# uBristleBot-Pogo-Programmer.net
KiCad netlist of a schematic drawn in EAGLE
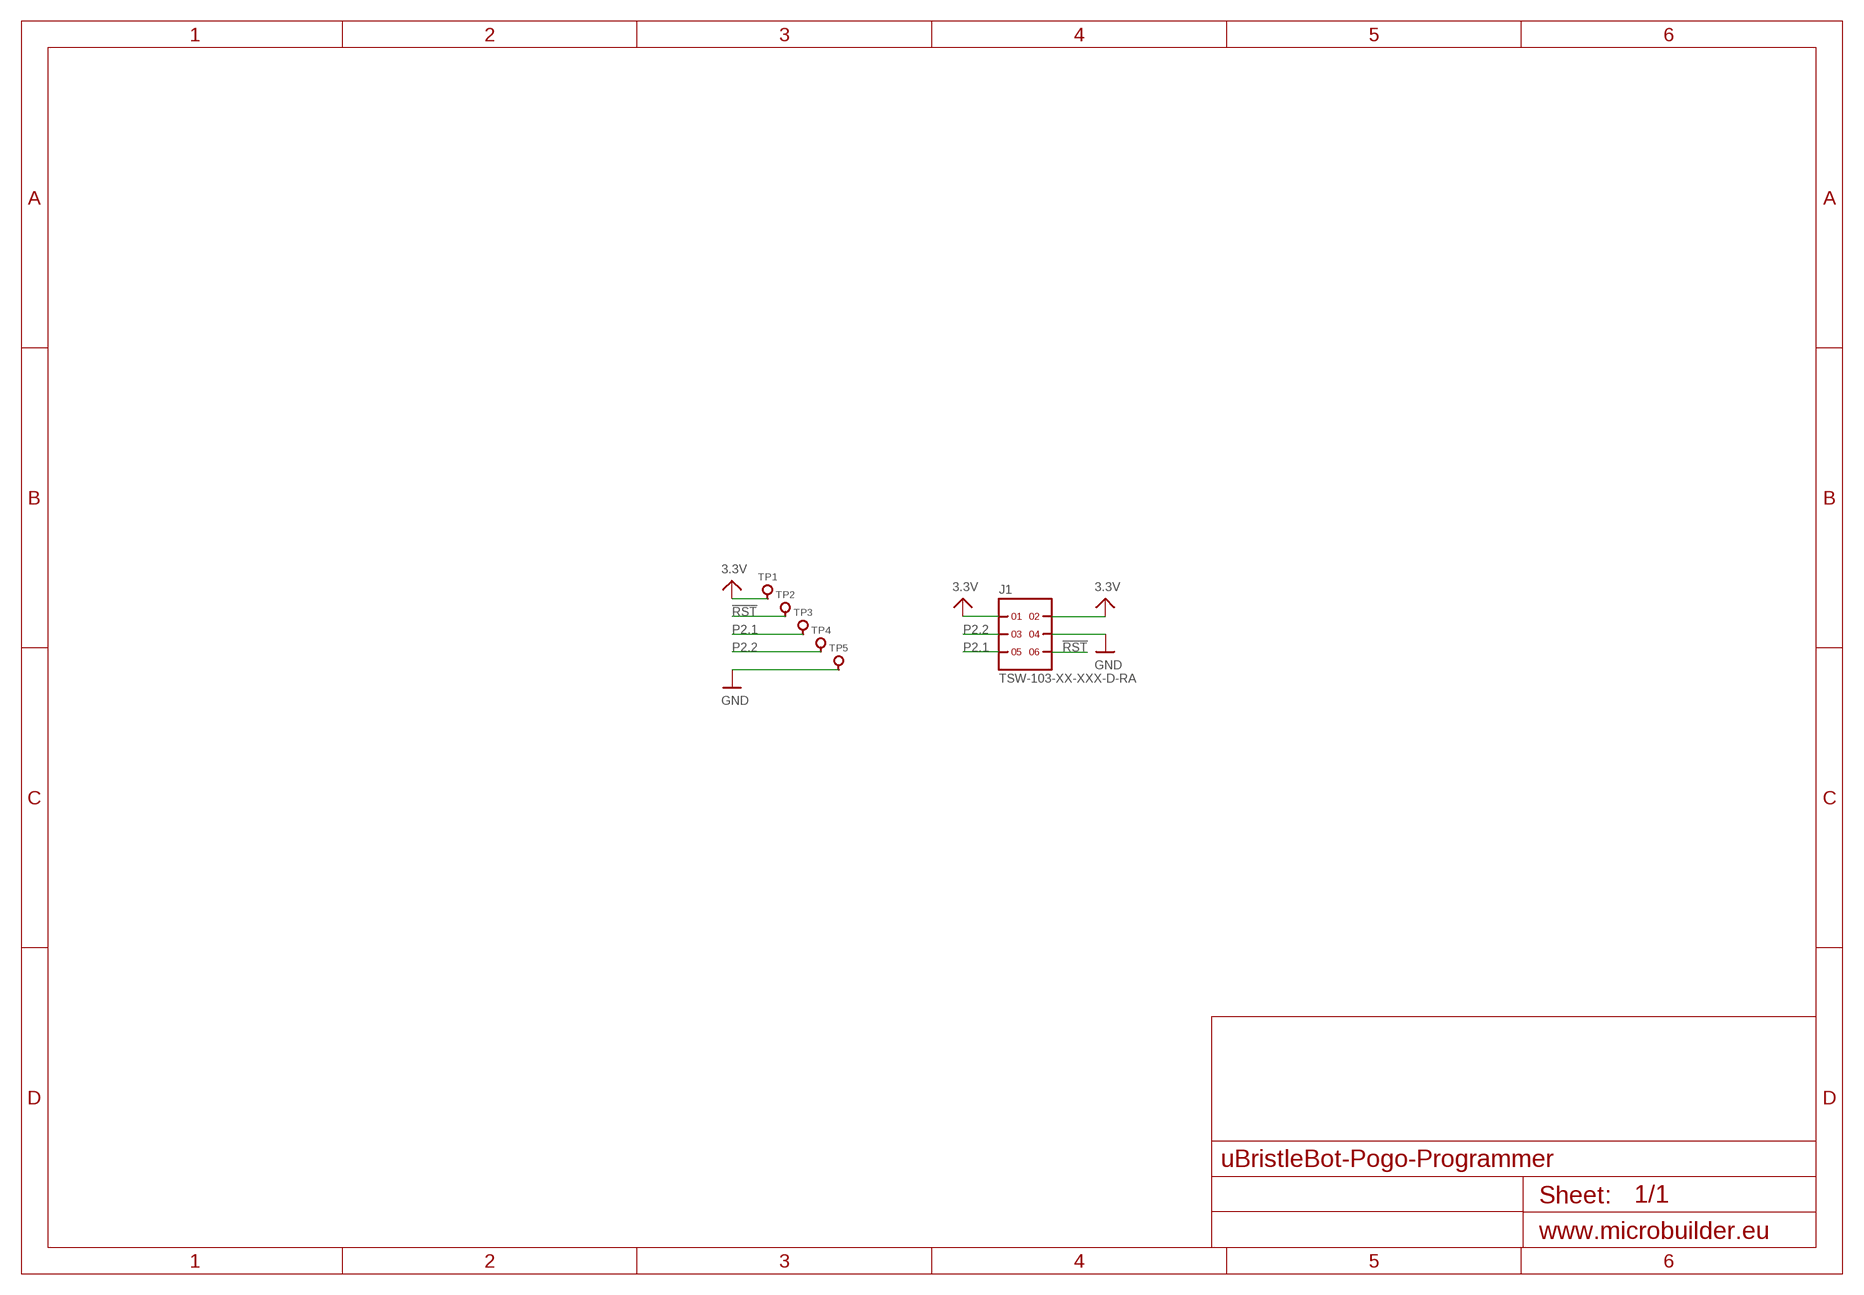
[diagram p0: schematic, sheet 1]

(export (version "E")
  (design (tool "Eeschema 10.0.6"))
  (components
    (comp (ref "J1")
      (value "TSW-103-XX-XXX-D-RA")
      (footprint "eagle-import:TSW-103-XX-XXX-D-RA")
      (libsource (lib "eagle-import") (part "TSW-103-XX-XXX-D-RA"))
    )
    (comp (ref "TP1")
      (value "0906-0")
      (footprint "eagle-import:0906-0")
      (libsource (lib "eagle-import") (part "0906-0"))
    )
    (comp (ref "TP2")
      (value "0906-0")
      (footprint "eagle-import:0906-0")
      (libsource (lib "eagle-import") (part "0906-0"))
    )
    (comp (ref "TP3")
      (value "0906-0")
      (footprint "eagle-import:0906-0")
      (libsource (lib "eagle-import") (part "0906-0"))
    )
    (comp (ref "TP4")
      (value "0906-0")
      (footprint "eagle-import:0906-0")
      (libsource (lib "eagle-import") (part "0906-0"))
    )
    (comp (ref "TP5")
      (value "0906-0")
      (footprint "eagle-import:0906-0")
      (libsource (lib "eagle-import") (part "0906-0"))
    )
  )
  (nets
    (net (code "1") (name "/P2.1") (class "Default")
      (node (ref "J1") (pin "5") (pinfunction "5_5") (pintype "bidirectional"))
      (node (ref "TP3") (pin "P$1") (pinfunction "PIN_P$1") (pintype "bidirectional"))
    )
    (net (code "2") (name "/P2.2") (class "Default")
      (node (ref "J1") (pin "3") (pinfunction "3_3") (pintype "bidirectional"))
      (node (ref "TP4") (pin "P$1") (pinfunction "PIN_P$1") (pintype "bidirectional"))
    )
    (net (code "3") (name "/~{RST}") (class "Default")
      (node (ref "J1") (pin "6") (pinfunction "6_6") (pintype "bidirectional"))
      (node (ref "TP2") (pin "P$1") (pinfunction "PIN_P$1") (pintype "bidirectional"))
    )
    (net (code "4") (name "3.3V") (class "Default")
      (node (ref "J1") (pin "1") (pinfunction "1_1") (pintype "bidirectional"))
      (node (ref "J1") (pin "2") (pinfunction "2_2") (pintype "bidirectional"))
      (node (ref "TP1") (pin "P$1") (pinfunction "PIN_P$1") (pintype "bidirectional"))
    )
    (net (code "5") (name "GND") (class "Default")
      (node (ref "J1") (pin "4") (pinfunction "4_4") (pintype "bidirectional"))
      (node (ref "TP5") (pin "P$1") (pinfunction "PIN_P$1") (pintype "bidirectional"))
    )
  )
)
